# V0.net
KiCad netlist of a schematic drawn in EAGLE
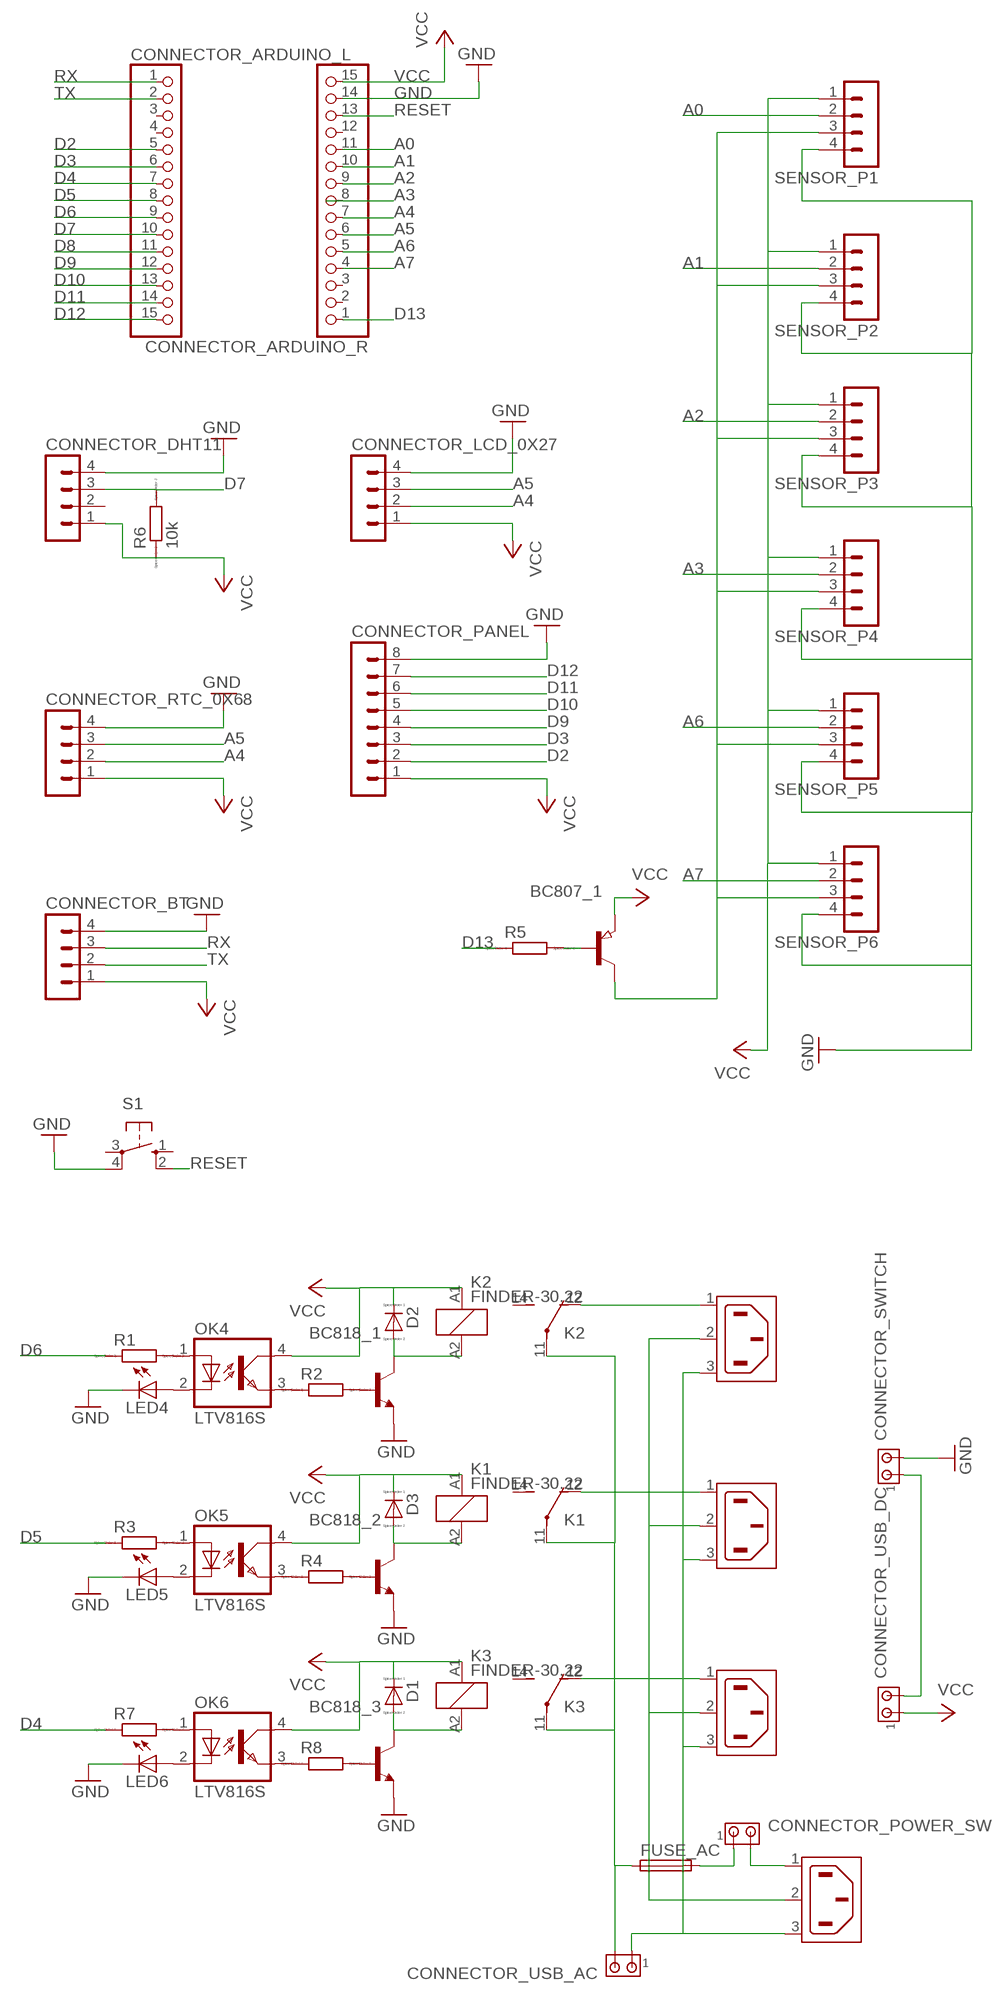
[diagram p0: schematic, sheet 1]

(export (version "E")
  (design (tool "Eeschema 10.0.6"))
  (components
    (comp (ref "BC807_1")
      (value "PNP-TRANSISTOR_SOT23")
      (footprint "eagle-import:SOT23")
      (libsource (lib "eagle-import") (part "PNP-TRANSISTOR_SOT23"))
    )
    (comp (ref "BC818_1")
      (value "BC847ASMD")
      (footprint "eagle-import:SOT23")
      (libsource (lib "eagle-import") (part "BC847SMDA"))
    )
    (comp (ref "BC818_2")
      (value "BC847ASMD")
      (footprint "eagle-import:SOT23")
      (libsource (lib "eagle-import") (part "BC847SMDA"))
    )
    (comp (ref "BC818_3")
      (value "BC847ASMD")
      (footprint "eagle-import:SOT23")
      (libsource (lib "eagle-import") (part "BC847SMDA"))
    )
    (comp (ref "CONNECTOR_ARDUINO_L")
      (value "PINHD-1X15")
      (footprint "eagle-import:1X15")
      (libsource (lib "eagle-import") (part "PINHD-1X15"))
    )
    (comp (ref "CONNECTOR_ARDUINO_R")
      (value "PINHD-1X15")
      (footprint "eagle-import:1X15")
      (libsource (lib "eagle-import") (part "PINHD-1X15"))
    )
    (comp (ref "CONNECTOR_BT")
      (value "MA04-1")
      (footprint "eagle-import:MA04-1")
      (libsource (lib "eagle-import") (part "MA04-1"))
    )
    (comp (ref "CONNECTOR_DHT11")
      (value "MA04-1")
      (footprint "eagle-import:MA04-1")
      (libsource (lib "eagle-import") (part "MA04-1"))
    )
    (comp (ref "CONNECTOR_LCD_0X27")
      (value "MA04-1")
      (footprint "eagle-import:MA04-1")
      (libsource (lib "eagle-import") (part "MA04-1"))
    )
    (comp (ref "CONNECTOR_PANEL")
      (value "MA08-1")
      (footprint "eagle-import:MA08-1")
      (libsource (lib "eagle-import") (part "MA08-1"))
    )
    (comp (ref "CONNECTOR_POWER_SWITCH")
      (value "MTA02-100")
      (footprint "eagle-import:10X02MTA")
      (libsource (lib "eagle-import") (part "MTA02-100"))
    )
    (comp (ref "CONNECTOR_RTC_0X68")
      (value "MA04-1")
      (footprint "eagle-import:MA04-1")
      (libsource (lib "eagle-import") (part "MA04-1"))
    )
    (comp (ref "CONNECTOR_SWITCH")
      (value "MTA02-100")
      (footprint "eagle-import:10X02MTA")
      (libsource (lib "eagle-import") (part "MTA02-100"))
    )
    (comp (ref "CONNECTOR_USB_AC")
      (value "MTA02-100")
      (footprint "eagle-import:10X02MTA")
      (libsource (lib "eagle-import") (part "MTA02-100"))
    )
    (comp (ref "CONNECTOR_USB_DC")
      (value "MTA02-100")
      (footprint "eagle-import:10X02MTA")
      (libsource (lib "eagle-import") (part "MTA02-100"))
    )
    (comp (ref "D1")
      (value "DIODE_E-")
      (footprint "eagle-import:DIODE_SMB")
      (libsource (lib "eagle-import") (part "DIODE_E-"))
    )
    (comp (ref "D2")
      (value "DIODE_E-")
      (footprint "eagle-import:DIODE_SMB")
      (libsource (lib "eagle-import") (part "DIODE_E-"))
    )
    (comp (ref "D3")
      (value "DIODE_E-")
      (footprint "eagle-import:DIODE_SMB")
      (libsource (lib "eagle-import") (part "DIODE_E-"))
    )
    (comp (ref "FUSE_AC")
      (value "SH22,5")
      (footprint "eagle-import:SH22,5")
      (fields (field (name "MF") "SCHURTER") (field (name "MPN") "0031.8201"))
      (libsource (lib "eagle-import") (part "SH22,5"))
    )
    (comp (ref "IN_AC")
      (value "6ESRM-P")
      (footprint "eagle-import:6ESRM-P")
      (fields (field (name "MF") "TYCO ELECTRONICS"))
      (libsource (lib "eagle-import") (part "6ESRM-P"))
    )
    (comp (ref "K1")
      (value "FINDER-30.22")
      (footprint "eagle-import:FINDER-30.22")
      (libsource (lib "eagle-import") (part "FINDER-30.22"))
    )
    (comp (ref "K2")
      (value "FINDER-30.22")
      (footprint "eagle-import:FINDER-30.22")
      (libsource (lib "eagle-import") (part "FINDER-30.22"))
    )
    (comp (ref "K3")
      (value "FINDER-30.22")
      (footprint "eagle-import:FINDER-30.22")
      (libsource (lib "eagle-import") (part "FINDER-30.22"))
    )
    (comp (ref "LED4")
      (value "LEDCHIPLED_0805")
      (footprint "eagle-import:CHIPLED_0805")
      (libsource (lib "eagle-import") (part "LEDCHIPLED_0805"))
    )
    (comp (ref "LED5")
      (value "LEDCHIPLED_0805")
      (footprint "eagle-import:CHIPLED_0805")
      (libsource (lib "eagle-import") (part "LEDCHIPLED_0805"))
    )
    (comp (ref "LED6")
      (value "LEDCHIPLED_0805")
      (footprint "eagle-import:CHIPLED_0805")
      (libsource (lib "eagle-import") (part "LEDCHIPLED_0805"))
    )
    (comp (ref "OK4")
      (value "LTV816S")
      (footprint "eagle-import:SMD4")
      (libsource (lib "eagle-import") (part "LTV816S"))
    )
    (comp (ref "OK5")
      (value "LTV816S")
      (footprint "eagle-import:SMD4")
      (libsource (lib "eagle-import") (part "LTV816S"))
    )
    (comp (ref "OK6")
      (value "LTV816S")
      (footprint "eagle-import:SMD4")
      (libsource (lib "eagle-import") (part "LTV816S"))
    )
    (comp (ref "OUT_LIGHT")
      (value "6ESRM-P")
      (footprint "eagle-import:6ESRM-P")
      (fields (field (name "MF") "TYCO ELECTRONICS"))
      (libsource (lib "eagle-import") (part "6ESRM-P"))
    )
    (comp (ref "OUT_PUMP")
      (value "6ESRM-P")
      (footprint "eagle-import:6ESRM-P")
      (fields (field (name "MF") "TYCO ELECTRONICS"))
      (libsource (lib "eagle-import") (part "6ESRM-P"))
    )
    (comp (ref "OUT_PUMP1")
      (value "6ESRM-P")
      (footprint "eagle-import:6ESRM-P")
      (fields (field (name "MF") "TYCO ELECTRONICS"))
      (libsource (lib "eagle-import") (part "6ESRM-P"))
    )
    (comp (ref "R1") (value "R") (footprint "eagle-import:R0805") (libsource (lib "eagle-import") (part "R")))
    (comp (ref "R2") (value "R") (footprint "eagle-import:R0805") (libsource (lib "eagle-import") (part "R")))
    (comp (ref "R3") (value "R") (footprint "eagle-import:R0805") (libsource (lib "eagle-import") (part "R")))
    (comp (ref "R4") (value "R") (footprint "eagle-import:R0805") (libsource (lib "eagle-import") (part "R")))
    (comp (ref "R5") (value "R") (footprint "eagle-import:R0805") (libsource (lib "eagle-import") (part "R")))
    (comp (ref "R6")
      (value "10k")
      (footprint "eagle-import:R0805")
      (libsource (lib "eagle-import") (part "R"))
    )
    (comp (ref "R7") (value "R") (footprint "eagle-import:R0805") (libsource (lib "eagle-import") (part "R")))
    (comp (ref "R8") (value "R") (footprint "eagle-import:R0805") (libsource (lib "eagle-import") (part "R")))
    (comp (ref "S1")
      (value "10-XX")
      (footprint "eagle-import:B3F-10XX")
      (fields (field (name "MPN") "B3F-1000"))
      (libsource (lib "eagle-import") (part "10-XX"))
    )
    (comp (ref "SENSOR_P1")
      (value "MA04-1")
      (footprint "eagle-import:MA04-1")
      (libsource (lib "eagle-import") (part "MA04-1"))
    )
    (comp (ref "SENSOR_P2")
      (value "MA04-1")
      (footprint "eagle-import:MA04-1")
      (libsource (lib "eagle-import") (part "MA04-1"))
    )
    (comp (ref "SENSOR_P3")
      (value "MA04-1")
      (footprint "eagle-import:MA04-1")
      (libsource (lib "eagle-import") (part "MA04-1"))
    )
    (comp (ref "SENSOR_P4")
      (value "MA04-1")
      (footprint "eagle-import:MA04-1")
      (libsource (lib "eagle-import") (part "MA04-1"))
    )
    (comp (ref "SENSOR_P5")
      (value "MA04-1")
      (footprint "eagle-import:MA04-1")
      (libsource (lib "eagle-import") (part "MA04-1"))
    )
    (comp (ref "SENSOR_P6")
      (value "MA04-1")
      (footprint "eagle-import:MA04-1")
      (libsource (lib "eagle-import") (part "MA04-1"))
    )
  )
  (nets
    (net (code "1") (name "/A0") (class "Default")
      (node (ref "CONNECTOR_ARDUINO_R") (pin "11") (pinfunction "11_11") (pintype "passive"))
      (node (ref "SENSOR_P1") (pin "2") (pinfunction "2_2") (pintype "passive"))
    )
    (net (code "2") (name "/A1") (class "Default")
      (node (ref "CONNECTOR_ARDUINO_R") (pin "10") (pinfunction "10_10") (pintype "passive"))
      (node (ref "SENSOR_P2") (pin "2") (pinfunction "2_2") (pintype "passive"))
    )
    (net (code "3") (name "/A2") (class "Default")
      (node (ref "CONNECTOR_ARDUINO_R") (pin "9") (pinfunction "9_9") (pintype "passive"))
      (node (ref "SENSOR_P3") (pin "2") (pinfunction "2_2") (pintype "passive"))
    )
    (net (code "4") (name "/A3") (class "Default")
      (node (ref "CONNECTOR_ARDUINO_R") (pin "8") (pinfunction "8_8") (pintype "passive"))
      (node (ref "SENSOR_P4") (pin "2") (pinfunction "2_2") (pintype "passive"))
    )
    (net (code "5") (name "/A4") (class "Default")
      (node (ref "CONNECTOR_ARDUINO_R") (pin "7") (pinfunction "7_7") (pintype "passive"))
      (node (ref "CONNECTOR_LCD_0X27") (pin "2") (pinfunction "2_2") (pintype "passive"))
      (node (ref "CONNECTOR_RTC_0X68") (pin "2") (pinfunction "2_2") (pintype "passive"))
    )
    (net (code "6") (name "/A5") (class "Default")
      (node (ref "CONNECTOR_ARDUINO_R") (pin "6") (pinfunction "6_6") (pintype "passive"))
      (node (ref "CONNECTOR_LCD_0X27") (pin "3") (pinfunction "3_3") (pintype "passive"))
      (node (ref "CONNECTOR_RTC_0X68") (pin "3") (pinfunction "3_3") (pintype "passive"))
    )
    (net (code "7") (name "/A6") (class "Default")
      (node (ref "CONNECTOR_ARDUINO_R") (pin "5") (pinfunction "5_5") (pintype "passive"))
      (node (ref "SENSOR_P5") (pin "2") (pinfunction "2_2") (pintype "passive"))
    )
    (net (code "8") (name "/A7") (class "Default")
      (node (ref "CONNECTOR_ARDUINO_R") (pin "4") (pinfunction "4_4") (pintype "passive"))
      (node (ref "SENSOR_P6") (pin "2") (pinfunction "2_2") (pintype "passive"))
    )
    (net (code "9") (name "/D2") (class "Default")
      (node (ref "CONNECTOR_ARDUINO_L") (pin "5") (pinfunction "5_5") (pintype "passive"))
      (node (ref "CONNECTOR_PANEL") (pin "2") (pinfunction "2_2") (pintype "passive"))
    )
    (net (code "10") (name "/D3") (class "Default")
      (node (ref "CONNECTOR_ARDUINO_L") (pin "6") (pinfunction "6_6") (pintype "passive"))
      (node (ref "CONNECTOR_PANEL") (pin "3") (pinfunction "3_3") (pintype "passive"))
    )
    (net (code "11") (name "/D4") (class "Default")
      (node (ref "CONNECTOR_ARDUINO_L") (pin "7") (pinfunction "7_7") (pintype "passive"))
      (node (ref "R7") (pin "1") (pinfunction "1_1") (pintype "passive"))
    )
    (net (code "12") (name "/D5") (class "Default")
      (node (ref "CONNECTOR_ARDUINO_L") (pin "8") (pinfunction "8_8") (pintype "passive"))
      (node (ref "R3") (pin "1") (pinfunction "1_1") (pintype "passive"))
    )
    (net (code "13") (name "/D6") (class "Default")
      (node (ref "CONNECTOR_ARDUINO_L") (pin "9") (pinfunction "9_9") (pintype "passive"))
      (node (ref "R1") (pin "1") (pinfunction "1_1") (pintype "passive"))
    )
    (net (code "14") (name "/D7") (class "Default")
      (node (ref "CONNECTOR_ARDUINO_L") (pin "10") (pinfunction "10_10") (pintype "passive"))
      (node (ref "CONNECTOR_DHT11") (pin "3") (pinfunction "3_3") (pintype "passive"))
      (node (ref "R6") (pin "2") (pinfunction "2_2") (pintype "passive"))
    )
    (net (code "15") (name "/D8") (class "Default")
      (node (ref "CONNECTOR_ARDUINO_L") (pin "11") (pinfunction "11_11") (pintype "passive"))
    )
    (net (code "16") (name "/D9") (class "Default")
      (node (ref "CONNECTOR_ARDUINO_L") (pin "12") (pinfunction "12_12") (pintype "passive"))
      (node (ref "CONNECTOR_PANEL") (pin "4") (pinfunction "4_4") (pintype "passive"))
    )
    (net (code "17") (name "/D10") (class "Default")
      (node (ref "CONNECTOR_ARDUINO_L") (pin "13") (pinfunction "13_13") (pintype "passive"))
      (node (ref "CONNECTOR_PANEL") (pin "5") (pinfunction "5_5") (pintype "passive"))
    )
    (net (code "18") (name "/D11") (class "Default")
      (node (ref "CONNECTOR_ARDUINO_L") (pin "14") (pinfunction "14_14") (pintype "passive"))
      (node (ref "CONNECTOR_PANEL") (pin "6") (pinfunction "6_6") (pintype "passive"))
    )
    (net (code "19") (name "/D12") (class "Default")
      (node (ref "CONNECTOR_ARDUINO_L") (pin "15") (pinfunction "15_15") (pintype "passive"))
      (node (ref "CONNECTOR_PANEL") (pin "7") (pinfunction "7_7") (pintype "passive"))
    )
    (net (code "20") (name "/D13") (class "Default")
      (node (ref "CONNECTOR_ARDUINO_R") (pin "1") (pinfunction "1_1") (pintype "passive"))
      (node (ref "R5") (pin "1") (pinfunction "1_1") (pintype "passive"))
    )
    (net (code "21") (name "/RESET") (class "Default")
      (node (ref "CONNECTOR_ARDUINO_R") (pin "13") (pinfunction "13_13") (pintype "passive"))
      (node (ref "S1") (pin "2") (pinfunction "S1_2") (pintype "passive"))
    )
    (net (code "22") (name "/RX") (class "Default")
      (node (ref "CONNECTOR_ARDUINO_L") (pin "1") (pinfunction "1_1") (pintype "passive"))
      (node (ref "CONNECTOR_BT") (pin "3") (pinfunction "3_3") (pintype "passive"))
    )
    (net (code "23") (name "/TX") (class "Default")
      (node (ref "CONNECTOR_ARDUINO_L") (pin "2") (pinfunction "2_2") (pintype "passive"))
      (node (ref "CONNECTOR_BT") (pin "2") (pinfunction "2_2") (pintype "passive"))
    )
    (net (code "24") (name "GND") (class "Default")
      (node (ref "BC818_1") (pin "2") (pinfunction "E_2") (pintype "passive"))
      (node (ref "BC818_2") (pin "2") (pinfunction "E_2") (pintype "passive"))
      (node (ref "BC818_3") (pin "2") (pinfunction "E_2") (pintype "passive"))
      (node (ref "CONNECTOR_ARDUINO_R") (pin "14") (pinfunction "14_14") (pintype "passive"))
      (node (ref "CONNECTOR_BT") (pin "4") (pinfunction "4_4") (pintype "passive"))
      (node (ref "CONNECTOR_DHT11") (pin "4") (pinfunction "4_4") (pintype "passive"))
      (node (ref "CONNECTOR_LCD_0X27") (pin "4") (pinfunction "4_4") (pintype "passive"))
      (node (ref "CONNECTOR_PANEL") (pin "8") (pinfunction "8_8") (pintype "passive"))
      (node (ref "CONNECTOR_RTC_0X68") (pin "4") (pinfunction "4_4") (pintype "passive"))
      (node (ref "CONNECTOR_SWITCH") (pin "2") (pinfunction "2_2") (pintype "passive"))
      (node (ref "LED4") (pin "C") (pinfunction "C_C") (pintype "passive"))
      (node (ref "LED5") (pin "C") (pinfunction "C_C") (pintype "passive"))
      (node (ref "LED6") (pin "C") (pinfunction "C_C") (pintype "passive"))
      (node (ref "S1") (pin "4") (pinfunction "P1_4") (pintype "passive"))
      (node (ref "SENSOR_P1") (pin "4") (pinfunction "4_4") (pintype "passive"))
      (node (ref "SENSOR_P2") (pin "4") (pinfunction "4_4") (pintype "passive"))
      (node (ref "SENSOR_P3") (pin "4") (pinfunction "4_4") (pintype "passive"))
      (node (ref "SENSOR_P4") (pin "4") (pinfunction "4_4") (pintype "passive"))
      (node (ref "SENSOR_P5") (pin "4") (pinfunction "4_4") (pintype "passive"))
      (node (ref "SENSOR_P6") (pin "4") (pinfunction "4_4") (pintype "passive"))
    )
    (net (code "25") (name "Net-(BC807_1-B)") (class "Default")
      (node (ref "BC807_1") (pin "1") (pinfunction "B_1") (pintype "passive"))
      (node (ref "R5") (pin "2") (pinfunction "2_2") (pintype "passive"))
    )
    (net (code "26") (name "Net-(BC807_1-C)") (class "Default")
      (node (ref "BC807_1") (pin "3") (pinfunction "C_3") (pintype "passive"))
      (node (ref "SENSOR_P1") (pin "3") (pinfunction "3_3") (pintype "passive"))
      (node (ref "SENSOR_P2") (pin "3") (pinfunction "3_3") (pintype "passive"))
      (node (ref "SENSOR_P3") (pin "3") (pinfunction "3_3") (pintype "passive"))
      (node (ref "SENSOR_P4") (pin "3") (pinfunction "3_3") (pintype "passive"))
      (node (ref "SENSOR_P5") (pin "3") (pinfunction "3_3") (pintype "passive"))
      (node (ref "SENSOR_P6") (pin "3") (pinfunction "3_3") (pintype "passive"))
    )
    (net (code "27") (name "Net-(BC818_1-B)") (class "Default")
      (node (ref "BC818_1") (pin "1") (pinfunction "B_1") (pintype "passive"))
      (node (ref "R2") (pin "2") (pinfunction "2_2") (pintype "passive"))
    )
    (net (code "28") (name "Net-(BC818_1-C)") (class "Default")
      (node (ref "BC818_1") (pin "3") (pinfunction "C_3") (pintype "passive"))
      (node (ref "D2") (pin "A") (pinfunction "C_A") (pintype "passive"))
      (node (ref "K2") (pin "A2") (pinfunction "2_A2") (pintype "passive"))
    )
    (net (code "29") (name "Net-(BC818_2-B)") (class "Default")
      (node (ref "BC818_2") (pin "1") (pinfunction "B_1") (pintype "passive"))
      (node (ref "R4") (pin "2") (pinfunction "2_2") (pintype "passive"))
    )
    (net (code "30") (name "Net-(BC818_2-C)") (class "Default")
      (node (ref "BC818_2") (pin "3") (pinfunction "C_3") (pintype "passive"))
      (node (ref "D3") (pin "A") (pinfunction "C_A") (pintype "passive"))
      (node (ref "K1") (pin "A2") (pinfunction "2_A2") (pintype "passive"))
    )
    (net (code "31") (name "Net-(BC818_3-B)") (class "Default")
      (node (ref "BC818_3") (pin "1") (pinfunction "B_1") (pintype "passive"))
      (node (ref "R8") (pin "2") (pinfunction "2_2") (pintype "passive"))
    )
    (net (code "32") (name "Net-(BC818_3-C)") (class "Default")
      (node (ref "BC818_3") (pin "3") (pinfunction "C_3") (pintype "passive"))
      (node (ref "D1") (pin "A") (pinfunction "C_A") (pintype "passive"))
      (node (ref "K3") (pin "A2") (pinfunction "2_A2") (pintype "passive"))
    )
    (net (code "33") (name "Net-(CONNECTOR_POWER_SWITCH-Pad1)") (class "Default")
      (node (ref "CONNECTOR_POWER_SWITCH") (pin "1") (pinfunction "1_1") (pintype "passive"))
      (node (ref "FUSE_AC") (pin "2") (pinfunction "2_2") (pintype "passive"))
    )
    (net (code "34") (name "Net-(CONNECTOR_SWITCH-Pad1)") (class "Default")
      (node (ref "CONNECTOR_SWITCH") (pin "1") (pinfunction "1_1") (pintype "passive"))
      (node (ref "CONNECTOR_USB_DC") (pin "2") (pinfunction "2_2") (pintype "passive"))
    )
    (net (code "35") (name "Net-(IN_AC-AC1)") (class "Default")
      (node (ref "CONNECTOR_POWER_SWITCH") (pin "2") (pinfunction "2_2") (pintype "passive"))
      (node (ref "IN_AC") (pin "1") (pinfunction "AC1_1") (pintype "passive"))
    )
    (net (code "36") (name "Net-(IN_AC-AC2)") (class "Default")
      (node (ref "CONNECTOR_USB_AC") (pin "1") (pinfunction "1_1") (pintype "passive"))
      (node (ref "IN_AC") (pin "3") (pinfunction "AC2_3") (pintype "passive"))
      (node (ref "OUT_LIGHT") (pin "3") (pinfunction "AC2_3") (pintype "passive"))
      (node (ref "OUT_PUMP") (pin "3") (pinfunction "AC2_3") (pintype "passive"))
      (node (ref "OUT_PUMP1") (pin "3") (pinfunction "AC2_3") (pintype "passive"))
    )
    (net (code "37") (name "Net-(IN_AC-SH)") (class "Default")
      (node (ref "IN_AC") (pin "2") (pinfunction "SH_2") (pintype "passive"))
      (node (ref "OUT_LIGHT") (pin "2") (pinfunction "SH_2") (pintype "passive"))
      (node (ref "OUT_PUMP") (pin "2") (pinfunction "SH_2") (pintype "passive"))
      (node (ref "OUT_PUMP1") (pin "2") (pinfunction "SH_2") (pintype "passive"))
    )
    (net (code "38") (name "Net-(K1A-O)") (class "Default")
      (node (ref "K1") (pin "12") (pinfunction "O_12") (pintype "passive"))
      (node (ref "OUT_PUMP") (pin "1") (pinfunction "AC1_1") (pintype "passive"))
    )
    (net (code "39") (name "Net-(K1A-P)") (class "Default")
      (node (ref "CONNECTOR_USB_AC") (pin "2") (pinfunction "2_2") (pintype "passive"))
      (node (ref "FUSE_AC") (pin "1") (pinfunction "1_1") (pintype "passive"))
      (node (ref "K1") (pin "11") (pinfunction "P_11") (pintype "passive"))
      (node (ref "K2") (pin "11") (pinfunction "P_11") (pintype "passive"))
      (node (ref "K3") (pin "11") (pinfunction "P_11") (pintype "passive"))
    )
    (net (code "40") (name "Net-(K2A-O)") (class "Default")
      (node (ref "K2") (pin "12") (pinfunction "O_12") (pintype "passive"))
      (node (ref "OUT_LIGHT") (pin "1") (pinfunction "AC1_1") (pintype "passive"))
    )
    (net (code "41") (name "Net-(K3A-O)") (class "Default")
      (node (ref "K3") (pin "12") (pinfunction "O_12") (pintype "passive"))
      (node (ref "OUT_PUMP1") (pin "1") (pinfunction "AC1_1") (pintype "passive"))
    )
    (net (code "42") (name "Net-(OK4-A)") (class "Default")
      (node (ref "OK4") (pin "1") (pinfunction "A_1") (pintype "passive"))
      (node (ref "R1") (pin "2") (pinfunction "2_2") (pintype "passive"))
    )
    (net (code "43") (name "Net-(OK4-C)") (class "Default")
      (node (ref "LED4") (pin "A") (pinfunction "A_A") (pintype "passive"))
      (node (ref "OK4") (pin "2") (pinfunction "C_2") (pintype "passive"))
    )
    (net (code "44") (name "Net-(OK4-EMIT)") (class "Default")
      (node (ref "OK4") (pin "3") (pinfunction "EMIT_3") (pintype "passive"))
      (node (ref "R2") (pin "1") (pinfunction "1_1") (pintype "passive"))
    )
    (net (code "45") (name "Net-(OK5-A)") (class "Default")
      (node (ref "OK5") (pin "1") (pinfunction "A_1") (pintype "passive"))
      (node (ref "R3") (pin "2") (pinfunction "2_2") (pintype "passive"))
    )
    (net (code "46") (name "Net-(OK5-C)") (class "Default")
      (node (ref "LED5") (pin "A") (pinfunction "A_A") (pintype "passive"))
      (node (ref "OK5") (pin "2") (pinfunction "C_2") (pintype "passive"))
    )
    (net (code "47") (name "Net-(OK5-EMIT)") (class "Default")
      (node (ref "OK5") (pin "3") (pinfunction "EMIT_3") (pintype "passive"))
      (node (ref "R4") (pin "1") (pinfunction "1_1") (pintype "passive"))
    )
    (net (code "48") (name "Net-(OK6-A)") (class "Default")
      (node (ref "OK6") (pin "1") (pinfunction "A_1") (pintype "passive"))
      (node (ref "R7") (pin "2") (pinfunction "2_2") (pintype "passive"))
    )
    (net (code "49") (name "Net-(OK6-C)") (class "Default")
      (node (ref "LED6") (pin "A") (pinfunction "A_A") (pintype "passive"))
      (node (ref "OK6") (pin "2") (pinfunction "C_2") (pintype "passive"))
    )
    (net (code "50") (name "Net-(OK6-EMIT)") (class "Default")
      (node (ref "OK6") (pin "3") (pinfunction "EMIT_3") (pintype "passive"))
      (node (ref "R8") (pin "1") (pinfunction "1_1") (pintype "passive"))
    )
    (net (code "51") (name "VCC") (class "Default")
      (node (ref "BC807_1") (pin "2") (pinfunction "E_2") (pintype "passive"))
      (node (ref "CONNECTOR_ARDUINO_R") (pin "15") (pinfunction "15_15") (pintype "passive"))
      (node (ref "CONNECTOR_BT") (pin "1") (pinfunction "1_1") (pintype "passive"))
      (node (ref "CONNECTOR_DHT11") (pin "1") (pinfunction "1_1") (pintype "passive"))
      (node (ref "CONNECTOR_LCD_0X27") (pin "1") (pinfunction "1_1") (pintype "passive"))
      (node (ref "CONNECTOR_PANEL") (pin "1") (pinfunction "1_1") (pintype "passive"))
      (node (ref "CONNECTOR_RTC_0X68") (pin "1") (pinfunction "1_1") (pintype "passive"))
      (node (ref "CONNECTOR_USB_DC") (pin "1") (pinfunction "1_1") (pintype "passive"))
      (node (ref "D1") (pin "C") (pinfunction "A_C") (pintype "passive"))
      (node (ref "D2") (pin "C") (pinfunction "A_C") (pintype "passive"))
      (node (ref "D3") (pin "C") (pinfunction "A_C") (pintype "passive"))
      (node (ref "K1") (pin "A1") (pinfunction "1_A1") (pintype "passive"))
      (node (ref "K2") (pin "A1") (pinfunction "1_A1") (pintype "passive"))
      (node (ref "K3") (pin "A1") (pinfunction "1_A1") (pintype "passive"))
      (node (ref "OK4") (pin "4") (pinfunction "COL_4") (pintype "passive"))
      (node (ref "OK5") (pin "4") (pinfunction "COL_4") (pintype "passive"))
      (node (ref "OK6") (pin "4") (pinfunction "COL_4") (pintype "passive"))
      (node (ref "R6") (pin "1") (pinfunction "1_1") (pintype "passive"))
      (node (ref "SENSOR_P1") (pin "1") (pinfunction "1_1") (pintype "passive"))
      (node (ref "SENSOR_P2") (pin "1") (pinfunction "1_1") (pintype "passive"))
      (node (ref "SENSOR_P3") (pin "1") (pinfunction "1_1") (pintype "passive"))
      (node (ref "SENSOR_P4") (pin "1") (pinfunction "1_1") (pintype "passive"))
      (node (ref "SENSOR_P5") (pin "1") (pinfunction "1_1") (pintype "passive"))
      (node (ref "SENSOR_P6") (pin "1") (pinfunction "1_1") (pintype "passive"))
    )
    (net (code "52") (name "unconnected-(CONNECTOR_ARDUINO_L-Pad3)") (class "Default")
      (node (ref "CONNECTOR_ARDUINO_L") (pin "3") (pinfunction "3_3") (pintype "passive"))
    )
    (net (code "53") (name "unconnected-(CONNECTOR_ARDUINO_L-Pad4)") (class "Default")
      (node (ref "CONNECTOR_ARDUINO_L") (pin "4") (pinfunction "4_4") (pintype "passive"))
    )
    (net (code "54") (name "unconnected-(CONNECTOR_ARDUINO_R-Pad2)") (class "Default")
      (node (ref "CONNECTOR_ARDUINO_R") (pin "2") (pinfunction "2_2") (pintype "passive"))
    )
    (net (code "55") (name "unconnected-(CONNECTOR_ARDUINO_R-Pad3)") (class "Default")
      (node (ref "CONNECTOR_ARDUINO_R") (pin "3") (pinfunction "3_3") (pintype "passive"))
    )
    (net (code "56") (name "unconnected-(CONNECTOR_ARDUINO_R-Pad12)") (class "Default")
      (node (ref "CONNECTOR_ARDUINO_R") (pin "12") (pinfunction "12_12") (pintype "passive"))
    )
    (net (code "57") (name "unconnected-(CONNECTOR_DHT11-Pad2)") (class "Default")
      (node (ref "CONNECTOR_DHT11") (pin "2") (pinfunction "2_2") (pintype "passive"))
    )
    (net (code "58") (name "unconnected-(K1A-S-Pad14)") (class "Default")
      (node (ref "K1") (pin "14") (pinfunction "S_14") (pintype "passive"))
    )
    (net (code "59") (name "unconnected-(K2A-S-Pad14)") (class "Default")
      (node (ref "K2") (pin "14") (pinfunction "S_14") (pintype "passive"))
    )
    (net (code "60") (name "unconnected-(K3A-S-Pad14)") (class "Default")
      (node (ref "K3") (pin "14") (pinfunction "S_14") (pintype "passive"))
    )
    (net (code "61") (name "unconnected-(S1-P-Pad3)") (class "Default")
      (node (ref "S1") (pin "3") (pinfunction "P_3") (pintype "passive"))
    )
    (net (code "62") (name "unconnected-(S1-S-Pad1)") (class "Default")
      (node (ref "S1") (pin "1") (pinfunction "S_1") (pintype "passive"))
    )
  )
)
